# Power.net
KiCad netlist of a schematic drawn in Altium Designer
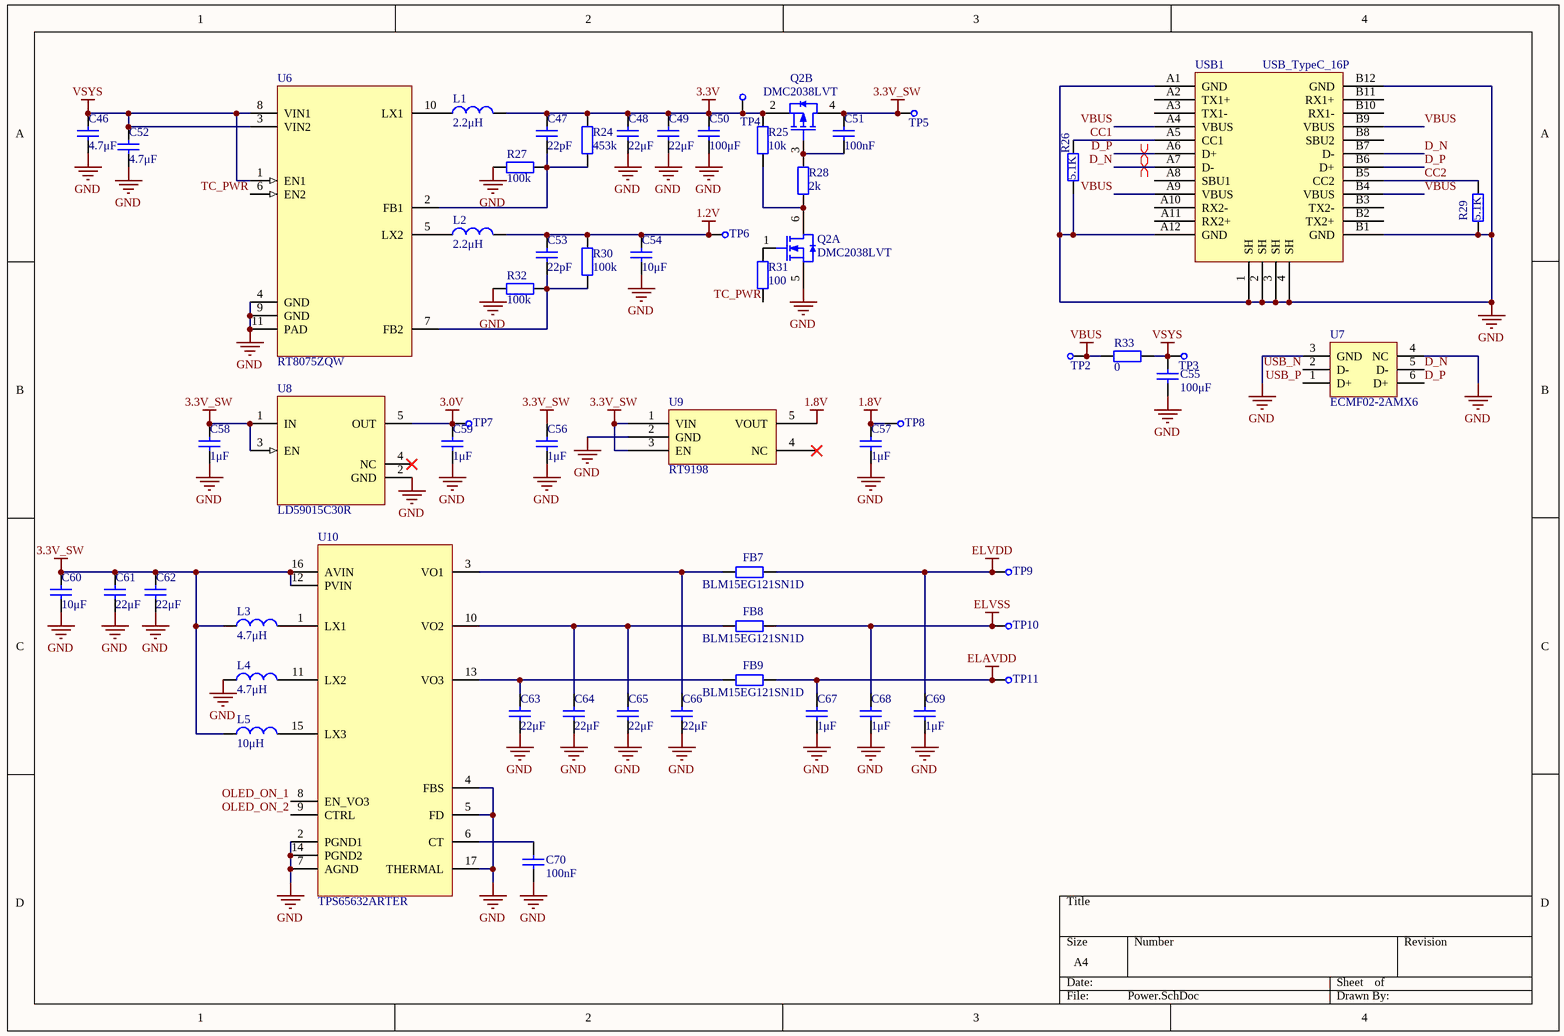
[diagram p0: Power.SchDoc]

(export (version "E")
  (design (tool "Eeschema 10.0.6"))
  (components
    (comp (ref "C46")
      (value "4.7μF")
      (footprint "0402C")
      (description "无极性电容")
      (fields (field (name "Comment") "Cap") (field (name "PUBLISHER") "Altium Limited"))
      (libsource (lib "Huskie") (part "Cap"))
    )
    (comp (ref "C47")
      (value "22pF")
      (footprint "0402C")
      (description "无极性电容")
      (fields (field (name "Comment") "Cap") (field (name "PUBLISHER") "Altium Limited"))
      (libsource (lib "Huskie") (part "Cap"))
    )
    (comp (ref "C48")
      (value "22μF")
      (footprint "0805C")
      (description "无极性电容")
      (fields (field (name "Comment") "Cap") (field (name "PUBLISHER") "Altium Limited"))
      (libsource (lib "Huskie") (part "Cap"))
    )
    (comp (ref "C49")
      (value "22μF")
      (footprint "0805C")
      (description "无极性电容")
      (fields (field (name "Comment") "Cap") (field (name "PUBLISHER") "Altium Limited"))
      (libsource (lib "Huskie") (part "Cap"))
    )
    (comp (ref "C50")
      (value "100μF")
      (footprint "1206C")
      (description "无极性电容")
      (fields (field (name "Comment") "Cap") (field (name "PUBLISHER") "Altium Limited"))
      (libsource (lib "Huskie") (part "Cap"))
    )
    (comp (ref "C51")
      (value "100nF")
      (footprint "0402C")
      (description "无极性电容")
      (fields (field (name "Comment") "Cap") (field (name "PUBLISHER") "Altium Limited"))
      (libsource (lib "Huskie") (part "Cap"))
    )
    (comp (ref "C52")
      (value "4.7μF")
      (footprint "0402C")
      (description "无极性电容")
      (fields (field (name "Comment") "Cap") (field (name "PUBLISHER") "Altium Limited"))
      (libsource (lib "Huskie") (part "Cap"))
    )
    (comp (ref "C53")
      (value "22pF")
      (footprint "0402C")
      (description "无极性电容")
      (fields (field (name "Comment") "Cap") (field (name "PUBLISHER") "Altium Limited"))
      (libsource (lib "Huskie") (part "Cap"))
    )
    (comp (ref "C54")
      (value "10μF")
      (footprint "0603C")
      (description "无极性电容")
      (fields (field (name "Comment") "Cap") (field (name "PUBLISHER") "Altium Limited"))
      (libsource (lib "Huskie") (part "Cap"))
    )
    (comp (ref "C55")
      (value "100μF")
      (footprint "1206C")
      (description "无极性电容")
      (fields (field (name "Comment") "Cap") (field (name "PUBLISHER") "Altium Limited"))
      (libsource (lib "Huskie") (part "Cap"))
    )
    (comp (ref "C56")
      (value "1μF")
      (footprint "0402C")
      (description "无极性电容")
      (fields (field (name "Comment") "Cap") (field (name "PUBLISHER") "Altium Limited"))
      (libsource (lib "Huskie") (part "Cap"))
    )
    (comp (ref "C57")
      (value "1μF")
      (footprint "0402C")
      (description "无极性电容")
      (fields (field (name "Comment") "Cap") (field (name "PUBLISHER") "Altium Limited"))
      (libsource (lib "Huskie") (part "Cap"))
    )
    (comp (ref "C58")
      (value "1μF")
      (footprint "0402C")
      (description "无极性电容")
      (fields (field (name "Comment") "Cap") (field (name "PUBLISHER") "Altium Limited"))
      (libsource (lib "Huskie") (part "Cap"))
    )
    (comp (ref "C59")
      (value "1μF")
      (footprint "0402C")
      (description "无极性电容")
      (fields (field (name "Comment") "Cap") (field (name "PUBLISHER") "Altium Limited"))
      (libsource (lib "Huskie") (part "Cap"))
    )
    (comp (ref "C60")
      (value "10μF")
      (footprint "0603C")
      (description "无极性电容")
      (fields (field (name "Comment") "Cap") (field (name "PUBLISHER") "Altium Limited"))
      (libsource (lib "Huskie") (part "Cap"))
    )
    (comp (ref "C61")
      (value "22μF")
      (footprint "0805C")
      (description "无极性电容")
      (fields (field (name "Comment") "Cap") (field (name "PUBLISHER") "Altium Limited"))
      (libsource (lib "Huskie") (part "Cap"))
    )
    (comp (ref "C62")
      (value "22μF")
      (footprint "0805C")
      (description "无极性电容")
      (fields (field (name "Comment") "Cap") (field (name "PUBLISHER") "Altium Limited"))
      (libsource (lib "Huskie") (part "Cap"))
    )
    (comp (ref "C63")
      (value "22μF")
      (footprint "0805C")
      (description "无极性电容")
      (fields (field (name "Comment") "Cap") (field (name "PUBLISHER") "Altium Limited"))
      (libsource (lib "Huskie") (part "Cap"))
    )
    (comp (ref "C64")
      (value "22μF")
      (footprint "0805C")
      (description "无极性电容")
      (fields (field (name "Comment") "Cap") (field (name "PUBLISHER") "Altium Limited"))
      (libsource (lib "Huskie") (part "Cap"))
    )
    (comp (ref "C65")
      (value "22μF")
      (footprint "0805C")
      (description "无极性电容")
      (fields (field (name "Comment") "Cap") (field (name "PUBLISHER") "Altium Limited"))
      (libsource (lib "Huskie") (part "Cap"))
    )
    (comp (ref "C66")
      (value "22μF")
      (footprint "0805C")
      (description "无极性电容")
      (fields (field (name "Comment") "Cap") (field (name "PUBLISHER") "Altium Limited"))
      (libsource (lib "Huskie") (part "Cap"))
    )
    (comp (ref "C67")
      (value "1μF")
      (footprint "0402C")
      (description "无极性电容")
      (fields (field (name "Comment") "Cap") (field (name "PUBLISHER") "Altium Limited"))
      (libsource (lib "Huskie") (part "Cap"))
    )
    (comp (ref "C68")
      (value "1μF")
      (footprint "0402C")
      (description "无极性电容")
      (fields (field (name "Comment") "Cap") (field (name "PUBLISHER") "Altium Limited"))
      (libsource (lib "Huskie") (part "Cap"))
    )
    (comp (ref "C69")
      (value "1μF")
      (footprint "0402C")
      (description "无极性电容")
      (fields (field (name "Comment") "Cap") (field (name "PUBLISHER") "Altium Limited"))
      (libsource (lib "Huskie") (part "Cap"))
    )
    (comp (ref "C70")
      (value "100nF")
      (footprint "0402C")
      (description "无极性电容")
      (fields (field (name "Comment") "Cap") (field (name "PUBLISHER") "Altium Limited"))
      (libsource (lib "Huskie") (part "Cap"))
    )
    (comp (ref "FB7")
      (value "BLM15EG121SN1D")
      (footprint "0402R")
      (description "电阻")
      (fields (field (name "Comment") "Resistor") (field (name "PUBLISHER") "Altium Limited"))
      (libsource (lib "") (part "Resistor_1"))
    )
    (comp (ref "FB8")
      (value "BLM15EG121SN1D")
      (footprint "0402R")
      (description "电阻")
      (fields (field (name "Comment") "Resistor") (field (name "PUBLISHER") "Altium Limited"))
      (libsource (lib "") (part "Resistor_1"))
    )
    (comp (ref "FB9")
      (value "BLM15EG121SN1D")
      (footprint "0402R")
      (description "电阻")
      (fields (field (name "Comment") "Resistor") (field (name "PUBLISHER") "Altium Limited"))
      (libsource (lib "") (part "Resistor_1"))
    )
    (comp (ref "L1")
      (value "2.2μH")
      (footprint "IND-SMD_L3.0-W3.0_FNR30XXS")
      (description "电感")
      (fields (field (name "Comment") "Inductor") (field (name "PUBLISHER") "Altium Limited"))
      (libsource (lib "Huskie") (part "Inductor"))
    )
    (comp (ref "L2")
      (value "2.2μH")
      (footprint "IND-SMD_L3.0-W3.0_FNR30XXS")
      (description "电感")
      (fields (field (name "Comment") "Inductor") (field (name "PUBLISHER") "Altium Limited"))
      (libsource (lib "Huskie") (part "Inductor"))
    )
    (comp (ref "L3")
      (value "4.7μH")
      (footprint "IND-SMD_L2.5-W2.0-1")
      (description "电感")
      (fields (field (name "Comment") "Inductor") (field (name "PUBLISHER") "Altium Limited"))
      (libsource (lib "Huskie") (part "Inductor"))
    )
    (comp (ref "L4")
      (value "4.7μH")
      (footprint "IND-SMD_L2.5-W2.0-1")
      (description "电感")
      (fields (field (name "Comment") "Inductor") (field (name "PUBLISHER") "Altium Limited"))
      (libsource (lib "Huskie") (part "Inductor"))
    )
    (comp (ref "L5")
      (value "10μH")
      (footprint "IND-SMD_L3.0-W3.0_FNR30XXS")
      (description "电感")
      (fields (field (name "Comment") "Inductor") (field (name "PUBLISHER") "Altium Limited"))
      (libsource (lib "Huskie") (part "Inductor"))
    )
    (comp (ref "Q2")
      (value "DMC2038LVT")
      (footprint "SOT-23-6")
      (description "Dual P + N MOS")
      (libsource (lib "Huskie") (part "DMC2038LVT"))
    )
    (comp (ref "R24")
      (value "453k")
      (footprint "0402R")
      (description "电阻")
      (fields (field (name "Comment") "Resistor") (field (name "PUBLISHER") "Altium Limited"))
      (libsource (lib "Huskie") (part "Resistor"))
    )
    (comp (ref "R25")
      (value "10k")
      (footprint "0402R")
      (description "电阻")
      (fields (field (name "Comment") "Resistor") (field (name "PUBLISHER") "Altium Limited"))
      (libsource (lib "") (part "Resistor_2"))
    )
    (comp (ref "R26")
      (value "5.1K")
      (footprint "0402R")
      (description "电阻")
      (fields (field (name "Comment") "Resistor") (field (name "PUBLISHER") "Altium Limited"))
      (libsource (lib "Huskie") (part "Resistor"))
    )
    (comp (ref "R27")
      (value "100k")
      (footprint "0402R")
      (description "电阻")
      (fields (field (name "Comment") "Resistor") (field (name "PUBLISHER") "Altium Limited"))
      (libsource (lib "") (part "Resistor_3"))
    )
    (comp (ref "R28")
      (value "2k")
      (footprint "0402R")
      (description "电阻")
      (fields (field (name "Comment") "Resistor") (field (name "PUBLISHER") "Altium Limited"))
      (libsource (lib "") (part "Resistor_2"))
    )
    (comp (ref "R29")
      (value "5.1K")
      (footprint "0402R")
      (description "电阻")
      (fields (field (name "Comment") "Resistor") (field (name "PUBLISHER") "Altium Limited"))
      (libsource (lib "Huskie") (part "Resistor"))
    )
    (comp (ref "R30")
      (value "100k")
      (footprint "0402R")
      (description "电阻")
      (fields (field (name "Comment") "Resistor") (field (name "PUBLISHER") "Altium Limited"))
      (libsource (lib "Huskie") (part "Resistor"))
    )
    (comp (ref "R31")
      (value "100")
      (footprint "0402R")
      (description "电阻")
      (fields (field (name "Comment") "Resistor") (field (name "PUBLISHER") "Altium Limited"))
      (libsource (lib "") (part "Resistor_2"))
    )
    (comp (ref "R32")
      (value "100k")
      (footprint "0402R")
      (description "电阻")
      (fields (field (name "Comment") "Resistor") (field (name "PUBLISHER") "Altium Limited"))
      (libsource (lib "") (part "Resistor_3"))
    )
    (comp (ref "R33")
      (value "0")
      (footprint "0805R")
      (description "电阻")
      (fields (field (name "Comment") "Resistor") (field (name "PUBLISHER") "Altium Limited"))
      (libsource (lib "") (part "Resistor_1"))
    )
    (comp (ref "TP2")
      (value "CHECK")
      (footprint "CHECK-B")
      (description "测试点")
      (libsource (lib "Huskie") (part "CHECK"))
    )
    (comp (ref "TP3")
      (value "CHECK")
      (footprint "CHECK-B")
      (description "测试点")
      (libsource (lib "Huskie") (part "CHECK"))
    )
    (comp (ref "TP4")
      (value "CHECK")
      (footprint "CHECK-B")
      (description "测试点")
      (libsource (lib "Huskie") (part "CHECK"))
    )
    (comp (ref "TP5")
      (value "CHECK")
      (footprint "CHECK-B")
      (description "测试点")
      (libsource (lib "Huskie") (part "CHECK"))
    )
    (comp (ref "TP6")
      (value "CHECK")
      (footprint "CHECK-B")
      (description "测试点")
      (libsource (lib "Huskie") (part "CHECK"))
    )
    (comp (ref "TP7")
      (value "CHECK")
      (footprint "CHECK-B")
      (description "测试点")
      (libsource (lib "Huskie") (part "CHECK"))
    )
    (comp (ref "TP8")
      (value "CHECK")
      (footprint "CHECK-B")
      (description "测试点")
      (libsource (lib "Huskie") (part "CHECK"))
    )
    (comp (ref "TP9")
      (value "CHECK")
      (footprint "CHECK-B")
      (description "测试点")
      (libsource (lib "Huskie") (part "CHECK"))
    )
    (comp (ref "TP10")
      (value "CHECK")
      (footprint "CHECK-B")
      (description "测试点")
      (libsource (lib "Huskie") (part "CHECK"))
    )
    (comp (ref "TP11")
      (value "CHECK")
      (footprint "CHECK-B")
      (description "测试点")
      (libsource (lib "Huskie") (part "CHECK"))
    )
    (comp (ref "U6")
      (value "RT8075ZQW")
      (footprint "DFN-10_L3.0_W3.0_P0.5")
      (description "IC, DUAL STEP DOWN CONVERTER, 1A, 1.25MHz")
      (fields (field (name "MANUFACTURER") "RICHTEK"))
      (libsource (lib "Huskie") (part "RT8075ZQW"))
    )
    (comp (ref "U7")
      (value "ECMF02-2AMX6")
      (footprint "DFN-6_L1.5_W1.7_P0.5")
      (description "IC, COMMON MODE FILTER WITH ESD PROTECTION FOR MIPI")
      (fields (field (name "MANUFACTURER") "STMICROELECTRONICS"))
      (libsource (lib "Huskie") (part "ECMF02-2AMX6"))
    )
    (comp (ref "U8")
      (value "LD59015C30R")
      (footprint "SC-70(SC-70-5)")
      (description "IC, LDO REGULATOR, 3.0V, 150mA, HIGH PSRR")
      (fields (field (name "MANUFACTURER") "STMICROELECTRONICS"))
      (libsource (lib "Huskie") (part "LD59015C30R"))
    )
    (comp (ref "U9")
      (value "RT9198")
      (footprint "SOT-23-5")
      (description "LDO")
      (libsource (lib "Huskie") (part "RT9198"))
    )
    (comp (ref "U10")
      (value "TPS65632ARTER")
      (footprint "QFN-16_L3.0_W3.0")
      (description "IC, TRIPLE OUTPUT AMOLED DISPLAY POWER SUPPLY")
      (fields (field (name "MANUFACTURER") "TEXAS INSTRUMENTS"))
      (libsource (lib "Huskie") (part "TPS65632ARTER"))
    )
    (comp (ref "USB1")
      (value "USB_TypeC_16P")
      (footprint "USB3.0-TYPE-C-SMD_16PIN-H-PITCH0.50")
      (description "TypeC Connector")
      (libsource (lib "Huskie") (part "USB_TypeC"))
    )
  )
  (nets
    (net (code "1") (name "/CC1") (class "Default")
      (node (ref "R26") (pin "2") (pinfunction "2_2") (pintype "passive"))
      (node (ref "USB1") (pin "A5") (pinfunction "CC1_A5") (pintype "passive"))
    )
    (net (code "2") (name "/CC2") (class "Default")
      (node (ref "R29") (pin "2") (pinfunction "2_2") (pintype "passive"))
      (node (ref "USB1") (pin "B5") (pinfunction "CC2_B5") (pintype "passive"))
    )
    (net (code "3") (name "/D_N") (class "Default")
      (node (ref "U7") (pin "5") (pinfunction "D-_5") (pintype "passive"))
      (node (ref "USB1") (pin "A7") (pinfunction "D-_A7") (pintype "passive"))
      (node (ref "USB1") (pin "B7") (pinfunction "D-_B7") (pintype "passive"))
    )
    (net (code "4") (name "/D_P") (class "Default")
      (node (ref "U7") (pin "6") (pinfunction "D+_6") (pintype "passive"))
      (node (ref "USB1") (pin "A6") (pinfunction "D+_A6") (pintype "passive"))
      (node (ref "USB1") (pin "B6") (pinfunction "D+_B6") (pintype "passive"))
    )
    (net (code "5") (name "/OLED_ON_1") (class "Default")
      (node (ref "U10") (pin "8") (pinfunction "EN_VO3_8") (pintype "passive"))
    )
    (net (code "6") (name "/OLED_ON_2") (class "Default")
      (node (ref "U10") (pin "9") (pinfunction "CTRL_9") (pintype "passive"))
    )
    (net (code "7") (name "/TC_PWR") (class "Default")
      (node (ref "R31") (pin "2") (pinfunction "2_2") (pintype "passive"))
      (node (ref "U6") (pin "6") (pinfunction "EN2_6") (pintype "input"))
    )
    (net (code "8") (name "/USB_N") (class "Default")
      (node (ref "U7") (pin "2") (pinfunction "D-_2") (pintype "passive"))
    )
    (net (code "9") (name "/USB_P") (class "Default")
      (node (ref "U7") (pin "1") (pinfunction "D+_1") (pintype "passive"))
    )
    (net (code "10") (name "1.2V") (class "Default")
      (node (ref "C53") (pin "2") (pinfunction "2_2") (pintype "passive"))
      (node (ref "C54") (pin "2") (pinfunction "2_2") (pintype "passive"))
      (node (ref "L2") (pin "2") (pinfunction "2_2") (pintype "passive"))
      (node (ref "R30") (pin "2") (pinfunction "2_2") (pintype "passive"))
      (node (ref "TP6") (pin "1") (pinfunction "1_1") (pintype "passive"))
    )
    (net (code "11") (name "1.8V") (class "Default")
      (node (ref "C57") (pin "2") (pinfunction "2_2") (pintype "passive"))
      (node (ref "TP8") (pin "1") (pinfunction "1_1") (pintype "passive"))
      (node (ref "U9") (pin "5") (pinfunction "VOUT_5") (pintype "passive"))
    )
    (net (code "12") (name "3.0V") (class "Default")
      (node (ref "C59") (pin "2") (pinfunction "2_2") (pintype "passive"))
      (node (ref "TP7") (pin "1") (pinfunction "1_1") (pintype "passive"))
      (node (ref "U8") (pin "5") (pinfunction "OUT_5") (pintype "power_in"))
    )
    (net (code "13") (name "3.3V") (class "Default")
      (node (ref "C47") (pin "2") (pinfunction "2_2") (pintype "passive"))
      (node (ref "C48") (pin "2") (pinfunction "2_2") (pintype "passive"))
      (node (ref "C49") (pin "2") (pinfunction "2_2") (pintype "passive"))
      (node (ref "C50") (pin "2") (pinfunction "2_2") (pintype "passive"))
      (node (ref "L1") (pin "2") (pinfunction "2_2") (pintype "passive"))
      (node (ref "Q2") (pin "2") (pinfunction "S_2") (pintype "passive"))
      (node (ref "R24") (pin "2") (pinfunction "2_2") (pintype "passive"))
      (node (ref "R25") (pin "1") (pinfunction "1_1") (pintype "passive"))
      (node (ref "TP4") (pin "1") (pinfunction "1_1") (pintype "passive"))
    )
    (net (code "14") (name "3.3V_SW") (class "Default")
      (node (ref "C51") (pin "2") (pinfunction "2_2") (pintype "passive"))
      (node (ref "C56") (pin "2") (pinfunction "2_2") (pintype "passive"))
      (node (ref "C58") (pin "2") (pinfunction "2_2") (pintype "passive"))
      (node (ref "C60") (pin "2") (pinfunction "2_2") (pintype "passive"))
      (node (ref "C61") (pin "2") (pinfunction "2_2") (pintype "passive"))
      (node (ref "C62") (pin "2") (pinfunction "2_2") (pintype "passive"))
      (node (ref "L3") (pin "1") (pinfunction "1_1") (pintype "passive"))
      (node (ref "L5") (pin "1") (pinfunction "1_1") (pintype "passive"))
      (node (ref "Q2") (pin "4") (pinfunction "D_4") (pintype "passive"))
      (node (ref "TP5") (pin "1") (pinfunction "1_1") (pintype "passive"))
      (node (ref "U10") (pin "12") (pinfunction "PVIN_12") (pintype "passive"))
      (node (ref "U10") (pin "16") (pinfunction "AVIN_16") (pintype "passive"))
      (node (ref "U8") (pin "1") (pinfunction "IN_1") (pintype "power_in"))
      (node (ref "U8") (pin "3") (pinfunction "EN_3") (pintype "input"))
      (node (ref "U9") (pin "1") (pinfunction "VIN_1") (pintype "passive"))
      (node (ref "U9") (pin "3") (pinfunction "EN_3") (pintype "passive"))
    )
    (net (code "15") (name "ELAVDD") (class "Default")
      (node (ref "C67") (pin "2") (pinfunction "2_2") (pintype "passive"))
      (node (ref "FB9") (pin "2") (pinfunction "2_2") (pintype "passive"))
      (node (ref "TP11") (pin "1") (pinfunction "1_1") (pintype "passive"))
    )
    (net (code "16") (name "ELVDD") (class "Default")
      (node (ref "C69") (pin "2") (pinfunction "2_2") (pintype "passive"))
      (node (ref "FB7") (pin "2") (pinfunction "2_2") (pintype "passive"))
      (node (ref "TP9") (pin "1") (pinfunction "1_1") (pintype "passive"))
    )
    (net (code "17") (name "ELVSS") (class "Default")
      (node (ref "C68") (pin "2") (pinfunction "2_2") (pintype "passive"))
      (node (ref "FB8") (pin "2") (pinfunction "2_2") (pintype "passive"))
      (node (ref "TP10") (pin "1") (pinfunction "1_1") (pintype "passive"))
    )
    (net (code "18") (name "GND") (class "Default")
      (node (ref "C46") (pin "1") (pinfunction "1_1") (pintype "passive"))
      (node (ref "C48") (pin "1") (pinfunction "1_1") (pintype "passive"))
      (node (ref "C49") (pin "1") (pinfunction "1_1") (pintype "passive"))
      (node (ref "C50") (pin "1") (pinfunction "1_1") (pintype "passive"))
      (node (ref "C52") (pin "1") (pinfunction "1_1") (pintype "passive"))
      (node (ref "C54") (pin "1") (pinfunction "1_1") (pintype "passive"))
      (node (ref "C55") (pin "1") (pinfunction "1_1") (pintype "passive"))
      (node (ref "C56") (pin "1") (pinfunction "1_1") (pintype "passive"))
      (node (ref "C57") (pin "1") (pinfunction "1_1") (pintype "passive"))
      (node (ref "C58") (pin "1") (pinfunction "1_1") (pintype "passive"))
      (node (ref "C59") (pin "1") (pinfunction "1_1") (pintype "passive"))
      (node (ref "C60") (pin "1") (pinfunction "1_1") (pintype "passive"))
      (node (ref "C61") (pin "1") (pinfunction "1_1") (pintype "passive"))
      (node (ref "C62") (pin "1") (pinfunction "1_1") (pintype "passive"))
      (node (ref "C63") (pin "1") (pinfunction "1_1") (pintype "passive"))
      (node (ref "C64") (pin "1") (pinfunction "1_1") (pintype "passive"))
      (node (ref "C65") (pin "1") (pinfunction "1_1") (pintype "passive"))
      (node (ref "C66") (pin "1") (pinfunction "1_1") (pintype "passive"))
      (node (ref "C67") (pin "1") (pinfunction "1_1") (pintype "passive"))
      (node (ref "C68") (pin "1") (pinfunction "1_1") (pintype "passive"))
      (node (ref "C69") (pin "1") (pinfunction "1_1") (pintype "passive"))
      (node (ref "C70") (pin "1") (pinfunction "1_1") (pintype "passive"))
      (node (ref "L4") (pin "1") (pinfunction "1_1") (pintype "passive"))
      (node (ref "Q2") (pin "5") (pinfunction "S_5") (pintype "passive"))
      (node (ref "R26") (pin "1") (pinfunction "1_1") (pintype "passive"))
      (node (ref "R27") (pin "2") (pinfunction "2_2") (pintype "passive"))
      (node (ref "R29") (pin "1") (pinfunction "1_1") (pintype "passive"))
      (node (ref "R32") (pin "2") (pinfunction "2_2") (pintype "passive"))
      (node (ref "U10") (pin "14") (pinfunction "PGND2_14") (pintype "passive"))
      (node (ref "U10") (pin "17") (pinfunction "THERMAL_17") (pintype "passive"))
      (node (ref "U10") (pin "2") (pinfunction "PGND1_2") (pintype "passive"))
      (node (ref "U10") (pin "4") (pinfunction "FBS_4") (pintype "passive"))
      (node (ref "U10") (pin "5") (pinfunction "FD_5") (pintype "passive"))
      (node (ref "U10") (pin "7") (pinfunction "AGND_7") (pintype "passive"))
      (node (ref "U6") (pin "11") (pinfunction "PAD_11") (pintype "power_in"))
      (node (ref "U6") (pin "4") (pinfunction "GND_4") (pintype "power_in"))
      (node (ref "U6") (pin "9") (pinfunction "GND_9") (pintype "power_in"))
      (node (ref "U7") (pin "3") (pinfunction "GND_3") (pintype "power_in"))
      (node (ref "U7") (pin "4") (pinfunction "NC_4") (pintype "power_in"))
      (node (ref "U8") (pin "2") (pinfunction "GND_2") (pintype "power_in"))
      (node (ref "U9") (pin "2") (pinfunction "GND_2") (pintype "passive"))
      (node (ref "USB1") (pin "1") (pinfunction "SH_1") (pintype "passive"))
      (node (ref "USB1") (pin "2") (pinfunction "SH_2") (pintype "passive"))
      (node (ref "USB1") (pin "3") (pinfunction "SH_3") (pintype "passive"))
      (node (ref "USB1") (pin "4") (pinfunction "SH_4") (pintype "passive"))
      (node (ref "USB1") (pin "A1") (pinfunction "GND_A1") (pintype "passive"))
      (node (ref "USB1") (pin "A12") (pinfunction "GND_A12") (pintype "passive"))
      (node (ref "USB1") (pin "B1") (pinfunction "GND_B1") (pintype "passive"))
      (node (ref "USB1") (pin "B12") (pinfunction "GND_B12") (pintype "passive"))
    )
    (net (code "19") (name "Net-(Q2A-D)") (class "Default")
      (node (ref "Q2") (pin "6") (pinfunction "D_6") (pintype "passive"))
      (node (ref "R25") (pin "2") (pinfunction "2_2") (pintype "passive"))
      (node (ref "R28") (pin "2") (pinfunction "2_2") (pintype "passive"))
    )
    (net (code "20") (name "Net-(Q2A-G)") (class "Default")
      (node (ref "Q2") (pin "1") (pinfunction "G_1") (pintype "passive"))
      (node (ref "R31") (pin "1") (pinfunction "1_1") (pintype "passive"))
    )
    (net (code "21") (name "Net-(Q2B-G)") (class "Default")
      (node (ref "C51") (pin "1") (pinfunction "1_1") (pintype "passive"))
      (node (ref "Q2") (pin "3") (pinfunction "G_3") (pintype "passive"))
      (node (ref "R28") (pin "1") (pinfunction "1_1") (pintype "passive"))
    )
    (net (code "22") (name "Net-(U6-FB1)") (class "Default")
      (node (ref "C47") (pin "1") (pinfunction "1_1") (pintype "passive"))
      (node (ref "R24") (pin "1") (pinfunction "1_1") (pintype "passive"))
      (node (ref "R27") (pin "1") (pinfunction "1_1") (pintype "passive"))
      (node (ref "U6") (pin "2") (pinfunction "FB1_2") (pintype "passive"))
    )
    (net (code "23") (name "Net-(U6-FB2)") (class "Default")
      (node (ref "C53") (pin "1") (pinfunction "1_1") (pintype "passive"))
      (node (ref "R30") (pin "1") (pinfunction "1_1") (pintype "passive"))
      (node (ref "R32") (pin "1") (pinfunction "1_1") (pintype "passive"))
      (node (ref "U6") (pin "7") (pinfunction "FB2_7") (pintype "passive"))
    )
    (net (code "24") (name "Net-(U6-LX1)") (class "Default")
      (node (ref "L1") (pin "1") (pinfunction "1_1") (pintype "passive"))
      (node (ref "U6") (pin "10") (pinfunction "LX1_10") (pintype "power_in"))
    )
    (net (code "25") (name "Net-(U6-LX2)") (class "Default")
      (node (ref "L2") (pin "1") (pinfunction "1_1") (pintype "passive"))
      (node (ref "U6") (pin "5") (pinfunction "LX2_5") (pintype "power_in"))
    )
    (net (code "26") (name "Net-(U10-CT)") (class "Default")
      (node (ref "C70") (pin "2") (pinfunction "2_2") (pintype "passive"))
      (node (ref "U10") (pin "6") (pinfunction "CT_6") (pintype "passive"))
    )
    (net (code "27") (name "Net-(U10-LX1)") (class "Default")
      (node (ref "L3") (pin "2") (pinfunction "2_2") (pintype "passive"))
      (node (ref "U10") (pin "1") (pinfunction "LX1_1") (pintype "passive"))
    )
    (net (code "28") (name "Net-(U10-LX2)") (class "Default")
      (node (ref "L4") (pin "2") (pinfunction "2_2") (pintype "passive"))
      (node (ref "U10") (pin "11") (pinfunction "LX2_11") (pintype "passive"))
    )
    (net (code "29") (name "Net-(U10-LX3)") (class "Default")
      (node (ref "L5") (pin "2") (pinfunction "2_2") (pintype "passive"))
      (node (ref "U10") (pin "15") (pinfunction "LX3_15") (pintype "passive"))
    )
    (net (code "30") (name "Net-(U10-VO1)") (class "Default")
      (node (ref "C66") (pin "2") (pinfunction "2_2") (pintype "passive"))
      (node (ref "FB7") (pin "1") (pinfunction "1_1") (pintype "passive"))
      (node (ref "U10") (pin "3") (pinfunction "VO1_3") (pintype "passive"))
    )
    (net (code "31") (name "Net-(U10-VO2)") (class "Default")
      (node (ref "C64") (pin "2") (pinfunction "2_2") (pintype "passive"))
      (node (ref "C65") (pin "2") (pinfunction "2_2") (pintype "passive"))
      (node (ref "FB8") (pin "1") (pinfunction "1_1") (pintype "passive"))
      (node (ref "U10") (pin "10") (pinfunction "VO2_10") (pintype "passive"))
    )
    (net (code "32") (name "Net-(U10-VO3)") (class "Default")
      (node (ref "C63") (pin "2") (pinfunction "2_2") (pintype "passive"))
      (node (ref "FB9") (pin "1") (pinfunction "1_1") (pintype "passive"))
      (node (ref "U10") (pin "13") (pinfunction "VO3_13") (pintype "passive"))
    )
    (net (code "33") (name "VBUS") (class "Default")
      (node (ref "R33") (pin "1") (pinfunction "1_1") (pintype "passive"))
      (node (ref "TP2") (pin "1") (pinfunction "1_1") (pintype "passive"))
      (node (ref "USB1") (pin "A4") (pinfunction "VBUS_A4") (pintype "passive"))
      (node (ref "USB1") (pin "A9") (pinfunction "VBUS_A9") (pintype "passive"))
      (node (ref "USB1") (pin "B4") (pinfunction "VBUS_B4") (pintype "passive"))
      (node (ref "USB1") (pin "B9") (pinfunction "VBUS_B9") (pintype "passive"))
    )
    (net (code "34") (name "VSYS") (class "Default")
      (node (ref "C46") (pin "2") (pinfunction "2_2") (pintype "passive"))
      (node (ref "C52") (pin "2") (pinfunction "2_2") (pintype "passive"))
      (node (ref "C55") (pin "2") (pinfunction "2_2") (pintype "passive"))
      (node (ref "R33") (pin "2") (pinfunction "2_2") (pintype "passive"))
      (node (ref "TP3") (pin "1") (pinfunction "1_1") (pintype "passive"))
      (node (ref "U6") (pin "1") (pinfunction "EN1_1") (pintype "input"))
      (node (ref "U6") (pin "3") (pinfunction "VIN2_3") (pintype "power_in"))
      (node (ref "U6") (pin "8") (pinfunction "VIN1_8") (pintype "power_in"))
    )
    (net (code "35") (name "unconnected-(U8-NC-Pad4)") (class "Default")
      (node (ref "U8") (pin "4") (pinfunction "NC_4") (pintype "power_in+no_connect"))
    )
    (net (code "36") (name "unconnected-(U9-NC-Pad4)") (class "Default")
      (node (ref "U9") (pin "4") (pinfunction "NC_4") (pintype "passive+no_connect"))
    )
    (net (code "37") (name "unconnected-(USB1-RX1+-PadB11)") (class "Default")
      (node (ref "USB1") (pin "B11") (pinfunction "RX1+_B11") (pintype "passive"))
    )
    (net (code "38") (name "unconnected-(USB1-RX1--PadB10)") (class "Default")
      (node (ref "USB1") (pin "B10") (pinfunction "RX1-_B10") (pintype "passive"))
    )
    (net (code "39") (name "unconnected-(USB1-RX2+-PadA11)") (class "Default")
      (node (ref "USB1") (pin "A11") (pinfunction "RX2+_A11") (pintype "passive"))
    )
    (net (code "40") (name "unconnected-(USB1-RX2--PadA10)") (class "Default")
      (node (ref "USB1") (pin "A10") (pinfunction "RX2-_A10") (pintype "passive"))
    )
    (net (code "41") (name "unconnected-(USB1-SBU1-PadA8)") (class "Default")
      (node (ref "USB1") (pin "A8") (pinfunction "SBU1_A8") (pintype "passive"))
    )
    (net (code "42") (name "unconnected-(USB1-SBU2-PadB8)") (class "Default")
      (node (ref "USB1") (pin "B8") (pinfunction "SBU2_B8") (pintype "passive"))
    )
    (net (code "43") (name "unconnected-(USB1-TX1+-PadA2)") (class "Default")
      (node (ref "USB1") (pin "A2") (pinfunction "TX1+_A2") (pintype "passive"))
    )
    (net (code "44") (name "unconnected-(USB1-TX1--PadA3)") (class "Default")
      (node (ref "USB1") (pin "A3") (pinfunction "TX1-_A3") (pintype "passive"))
    )
    (net (code "45") (name "unconnected-(USB1-TX2+-PadB2)") (class "Default")
      (node (ref "USB1") (pin "B2") (pinfunction "TX2+_B2") (pintype "passive"))
    )
    (net (code "46") (name "unconnected-(USB1-TX2--PadB3)") (class "Default")
      (node (ref "USB1") (pin "B3") (pinfunction "TX2-_B3") (pintype "passive"))
    )
  )
)
